# 06_-_FPGA_CONFIG_TEMP_MON.net
KiCad netlist of a schematic drawn in Altium Designer
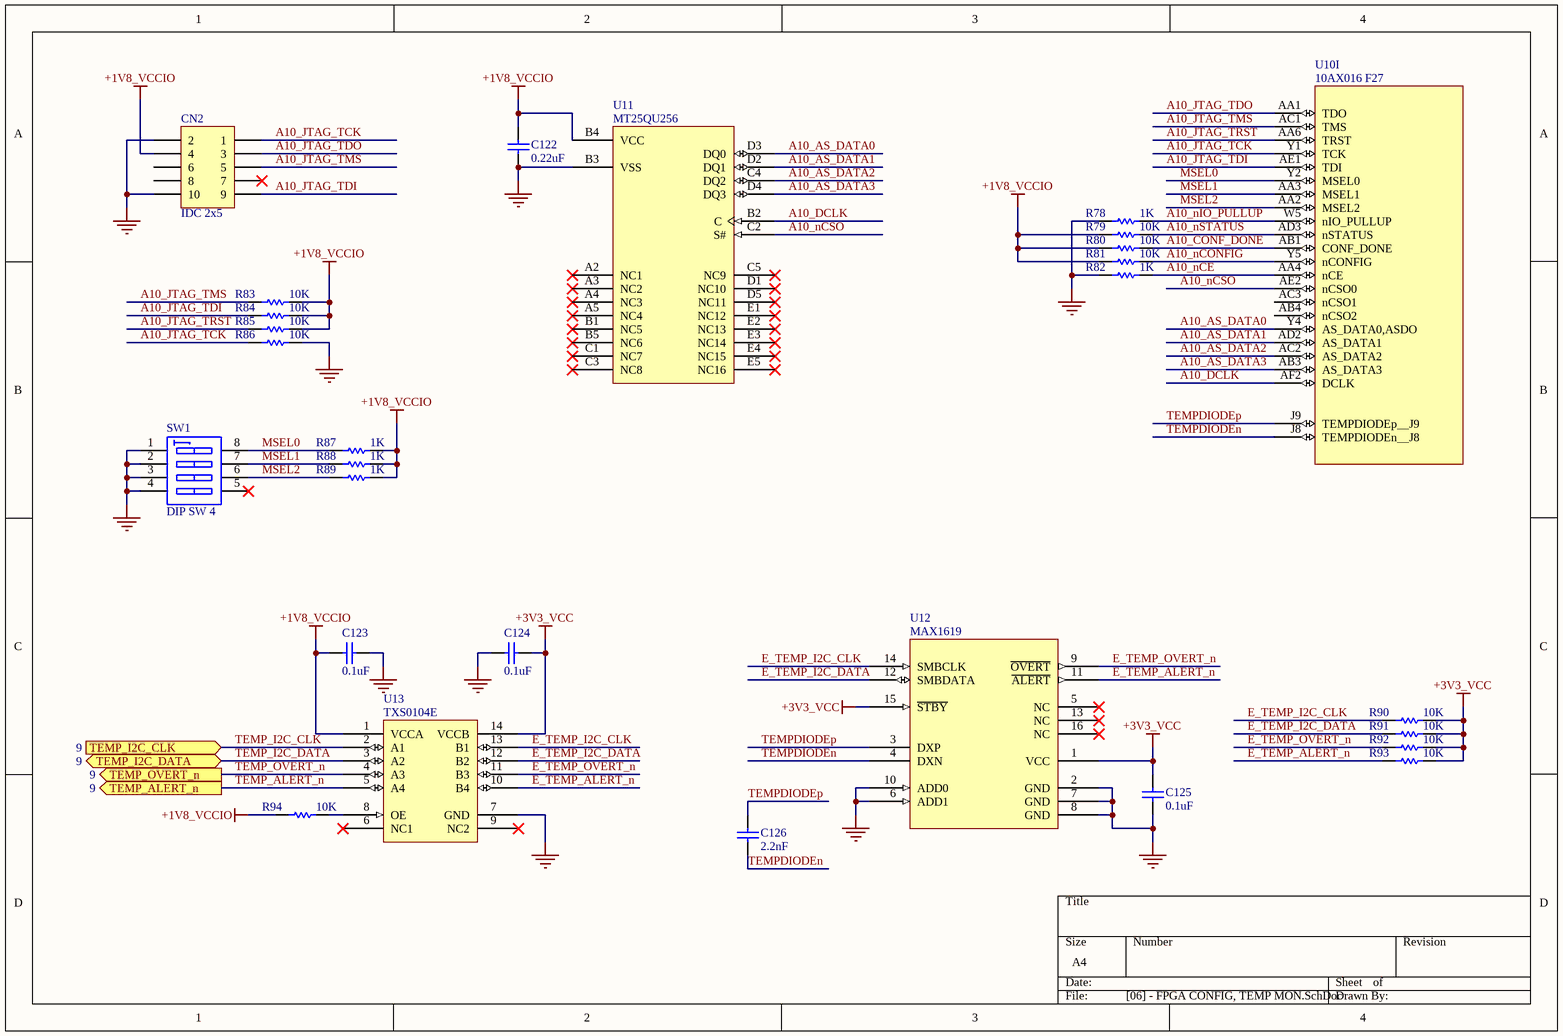
[diagram p0: [06] - FPGA CONFIG, TEMP MON.SchDoc]

(export (version "E")
  (design (tool "Eeschema 10.0.6"))
  (components
    (comp (ref "C122")
      (value "0.22uF")
      (footprint "0402_C")
      (description "Non-Pol SMD Capacitor")
      (libsource (lib "Passive Components") (part "Cap SMD"))
    )
    (comp (ref "C123")
      (value "0.1uF")
      (footprint "0805_C")
      (description "Non-Pol SMD Capacitor")
      (libsource (lib "Passive Components") (part "Cap SMD"))
    )
    (comp (ref "C124")
      (value "0.1uF")
      (footprint "0805_C")
      (description "Non-Pol SMD Capacitor")
      (libsource (lib "Passive Components") (part "Cap SMD"))
    )
    (comp (ref "C125")
      (value "0.1uF")
      (footprint "0805_C")
      (description "Non-Pol SMD Capacitor")
      (libsource (lib "Passive Components") (part "Cap SMD"))
    )
    (comp (ref "C126")
      (value "2.2nF")
      (footprint "0805_C")
      (description "Non-Pol SMD Capacitor")
      (libsource (lib "Passive Components") (part "Cap SMD"))
    )
    (comp (ref "CN2")
      (value "IDC 2x5")
      (footprint "IDC-BOX-2x5")
      (description "IDC Box, 5-Pin, Dual row")
      (libsource (lib "Connectors") (part "IDC 2x5"))
    )
    (comp (ref "R78")
      (value "1K")
      (footprint "0402_R")
      (description "SMD Resistor")
      (fields (field (name "TOLERANCE") "5%"))
      (libsource (lib "Passive Components") (part "Res SMD"))
    )
    (comp (ref "R79")
      (value "10K")
      (footprint "0402_R")
      (description "SMD Resistor")
      (fields (field (name "TOLERANCE") "5%"))
      (libsource (lib "Passive Components") (part "Res SMD"))
    )
    (comp (ref "R80")
      (value "10K")
      (footprint "0402_R")
      (description "SMD Resistor")
      (fields (field (name "TOLERANCE") "5%"))
      (libsource (lib "Passive Components") (part "Res SMD"))
    )
    (comp (ref "R81")
      (value "10K")
      (footprint "0402_R")
      (description "SMD Resistor")
      (fields (field (name "TOLERANCE") "5%"))
      (libsource (lib "Passive Components") (part "Res SMD"))
    )
    (comp (ref "R82")
      (value "1K")
      (footprint "0402_R")
      (description "SMD Resistor")
      (fields (field (name "TOLERANCE") "5%"))
      (libsource (lib "Passive Components") (part "Res SMD"))
    )
    (comp (ref "R83")
      (value "10K")
      (footprint "0402_R")
      (description "SMD Resistor")
      (fields (field (name "TOLERANCE") "5%"))
      (libsource (lib "Passive Components") (part "Res SMD"))
    )
    (comp (ref "R84")
      (value "10K")
      (footprint "0402_R")
      (description "SMD Resistor")
      (fields (field (name "TOLERANCE") "5%"))
      (libsource (lib "Passive Components") (part "Res SMD"))
    )
    (comp (ref "R85")
      (value "10K")
      (footprint "0402_R")
      (description "SMD Resistor")
      (fields (field (name "TOLERANCE") "5%"))
      (libsource (lib "Passive Components") (part "Res SMD"))
    )
    (comp (ref "R86")
      (value "10K")
      (footprint "0402_R")
      (description "SMD Resistor")
      (fields (field (name "TOLERANCE") "5%"))
      (libsource (lib "Passive Components") (part "Res SMD"))
    )
    (comp (ref "R87")
      (value "1K")
      (footprint "0402_R")
      (description "SMD Resistor")
      (fields (field (name "TOLERANCE") "5%"))
      (libsource (lib "Passive Components") (part "Res SMD"))
    )
    (comp (ref "R88")
      (value "1K")
      (footprint "0402_R")
      (description "SMD Resistor")
      (fields (field (name "TOLERANCE") "5%"))
      (libsource (lib "Passive Components") (part "Res SMD"))
    )
    (comp (ref "R89")
      (value "1K")
      (footprint "0402_R")
      (description "SMD Resistor")
      (fields (field (name "TOLERANCE") "5%"))
      (libsource (lib "Passive Components") (part "Res SMD"))
    )
    (comp (ref "R90")
      (value "10K")
      (footprint "0402_R")
      (description "SMD Resistor")
      (fields (field (name "TOLERANCE") "5%"))
      (libsource (lib "Passive Components") (part "Res SMD"))
    )
    (comp (ref "R91")
      (value "10K")
      (footprint "0402_R")
      (description "SMD Resistor")
      (fields (field (name "TOLERANCE") "5%"))
      (libsource (lib "Passive Components") (part "Res SMD"))
    )
    (comp (ref "R92")
      (value "10K")
      (footprint "0402_R")
      (description "SMD Resistor")
      (fields (field (name "TOLERANCE") "5%"))
      (libsource (lib "Passive Components") (part "Res SMD"))
    )
    (comp (ref "R93")
      (value "10K")
      (footprint "0402_R")
      (description "SMD Resistor")
      (fields (field (name "TOLERANCE") "5%"))
      (libsource (lib "Passive Components") (part "Res SMD"))
    )
    (comp (ref "R94")
      (value "10K")
      (footprint "0402_R")
      (description "SMD Resistor")
      (fields (field (name "TOLERANCE") "5%"))
      (libsource (lib "Passive Components") (part "Res SMD"))
    )
    (comp (ref "SW1")
      (value "DIP SW 4")
      (footprint "DIP-SW-4_1.27mm")
      (description "DIP Switch, 4 Position, SPST")
      (fields (field (name "MANUFACTURER PART NUM") "GDH04S04"))
      (libsource (lib "Passive Components") (part "DIP SW-4"))
    )
    (comp (ref "U10")
      (value "10AX016 F27")
      (footprint "FBGA672")
      (libsource (lib "Project_schlib") (part "10AX016"))
    )
    (comp (ref "U11")
      (value "MT25QU256")
      (description "Micron Serial NOR Flash Memory")
      (fields (field (name "MANUFACTURER PART NUM") "MT25QU256ABA8E12-1SIT"))
      (libsource (lib "Project_schlib") (part "MT25QU"))
    )
    (comp (ref "U12")
      (value "MAX1619")
      (description "Remote/Local Temperature Sensor")
      (libsource (lib "Project_schlib") (part "MAX1619"))
    )
    (comp (ref "U13")
      (value "TXS0104E")
      (description "4-Bit Bidirectional Voltage-Level Translator for Open-Drain and Push-Pull Applications")
      (libsource (lib "Project_schlib") (part "TXS0104E"))
    )
  )
  (nets
    (net (code "1") (name "+1V8_VCCIO") (class "Default")
      (node (ref "C122") (pin "2") (pinfunction "2_2") (pintype "passive"))
      (node (ref "C123") (pin "2") (pinfunction "2_2") (pintype "passive"))
      (node (ref "CN2") (pin "4") (pinfunction "4_4") (pintype "passive"))
      (node (ref "R79") (pin "1") (pinfunction "1_1") (pintype "passive"))
      (node (ref "R80") (pin "1") (pinfunction "1_1") (pintype "passive"))
      (node (ref "R81") (pin "1") (pinfunction "1_1") (pintype "passive"))
      (node (ref "R83") (pin "2") (pinfunction "2_2") (pintype "passive"))
      (node (ref "R84") (pin "2") (pinfunction "2_2") (pintype "passive"))
      (node (ref "R85") (pin "2") (pinfunction "2_2") (pintype "passive"))
      (node (ref "R87") (pin "2") (pinfunction "2_2") (pintype "passive"))
      (node (ref "R88") (pin "2") (pinfunction "2_2") (pintype "passive"))
      (node (ref "R89") (pin "2") (pinfunction "2_2") (pintype "passive"))
      (node (ref "R94") (pin "1") (pinfunction "1_1") (pintype "passive"))
      (node (ref "U11") (pin "B4") (pinfunction "VCC_B4") (pintype "power_in"))
      (node (ref "U13") (pin "1") (pinfunction "VCCA_1") (pintype "power_in"))
    )
    (net (code "2") (name "+3V3_VCC") (class "Default")
      (node (ref "C124") (pin "1") (pinfunction "1_1") (pintype "passive"))
      (node (ref "C125") (pin "2") (pinfunction "2_2") (pintype "passive"))
      (node (ref "R90") (pin "2") (pinfunction "2_2") (pintype "passive"))
      (node (ref "R91") (pin "2") (pinfunction "2_2") (pintype "passive"))
      (node (ref "R92") (pin "2") (pinfunction "2_2") (pintype "passive"))
      (node (ref "R93") (pin "2") (pinfunction "2_2") (pintype "passive"))
      (node (ref "U12") (pin "1") (pinfunction "VCC_1") (pintype "power_in"))
      (node (ref "U12") (pin "15") (pinfunction "~{STBY}_15") (pintype "input"))
      (node (ref "U13") (pin "14") (pinfunction "VCCB_14") (pintype "power_in"))
    )
    (net (code "3") (name "/A10_AS_DATA0") (class "Default")
      (node (ref "U10") (pin "Y4") (pinfunction "AS_DATA0,ASDO_Y4") (pintype "bidirectional"))
      (node (ref "U11") (pin "D3") (pinfunction "DQ0_D3") (pintype "bidirectional"))
    )
    (net (code "4") (name "/A10_AS_DATA1") (class "Default")
      (node (ref "U10") (pin "AD2") (pinfunction "AS_DATA1_AD2") (pintype "bidirectional"))
      (node (ref "U11") (pin "D2") (pinfunction "DQ1_D2") (pintype "bidirectional"))
    )
    (net (code "5") (name "/A10_AS_DATA2") (class "Default")
      (node (ref "U10") (pin "AC2") (pinfunction "AS_DATA2_AC2") (pintype "bidirectional"))
      (node (ref "U11") (pin "C4") (pinfunction "DQ2_C4") (pintype "bidirectional"))
    )
    (net (code "6") (name "/A10_AS_DATA3") (class "Default")
      (node (ref "U10") (pin "AB3") (pinfunction "AS_DATA3_AB3") (pintype "bidirectional"))
      (node (ref "U11") (pin "D4") (pinfunction "DQ3_D4") (pintype "bidirectional"))
    )
    (net (code "7") (name "/A10_CONF_DONE") (class "Default")
      (node (ref "R80") (pin "2") (pinfunction "2_2") (pintype "passive"))
      (node (ref "U10") (pin "AB1") (pinfunction "CONF_DONE_AB1") (pintype "bidirectional"))
    )
    (net (code "8") (name "/A10_DCLK") (class "Default")
      (node (ref "U10") (pin "AF2") (pinfunction "DCLK_AF2") (pintype "bidirectional"))
      (node (ref "U11") (pin "B2") (pinfunction "C_B2") (pintype "input"))
    )
    (net (code "9") (name "/A10_JTAG_TCK") (class "Default")
      (node (ref "CN2") (pin "1") (pinfunction "1_1") (pintype "passive"))
      (node (ref "R86") (pin "1") (pinfunction "1_1") (pintype "passive"))
      (node (ref "U10") (pin "Y1") (pinfunction "TCK_Y1") (pintype "bidirectional"))
    )
    (net (code "10") (name "/A10_JTAG_TDI") (class "Default")
      (node (ref "CN2") (pin "9") (pinfunction "9_9") (pintype "passive"))
      (node (ref "R84") (pin "1") (pinfunction "1_1") (pintype "passive"))
      (node (ref "U10") (pin "AE1") (pinfunction "TDI_AE1") (pintype "bidirectional"))
    )
    (net (code "11") (name "/A10_JTAG_TDO") (class "Default")
      (node (ref "CN2") (pin "3") (pinfunction "3_3") (pintype "passive"))
      (node (ref "U10") (pin "AA1") (pinfunction "TDO_AA1") (pintype "bidirectional"))
    )
    (net (code "12") (name "/A10_JTAG_TMS") (class "Default")
      (node (ref "CN2") (pin "5") (pinfunction "5_5") (pintype "passive"))
      (node (ref "R83") (pin "1") (pinfunction "1_1") (pintype "passive"))
      (node (ref "U10") (pin "AC1") (pinfunction "TMS_AC1") (pintype "bidirectional"))
    )
    (net (code "13") (name "/A10_JTAG_TRST") (class "Default")
      (node (ref "R85") (pin "1") (pinfunction "1_1") (pintype "passive"))
      (node (ref "U10") (pin "AA6") (pinfunction "TRST_AA6") (pintype "bidirectional"))
    )
    (net (code "14") (name "/A10_nCE") (class "Default")
      (node (ref "R82") (pin "2") (pinfunction "2_2") (pintype "passive"))
      (node (ref "U10") (pin "AA4") (pinfunction "nCE_AA4") (pintype "bidirectional"))
    )
    (net (code "15") (name "/A10_nCONFIG") (class "Default")
      (node (ref "R81") (pin "2") (pinfunction "2_2") (pintype "passive"))
      (node (ref "U10") (pin "Y5") (pinfunction "nCONFIG_Y5") (pintype "bidirectional"))
    )
    (net (code "16") (name "/A10_nCSO") (class "Default")
      (node (ref "U10") (pin "AE2") (pinfunction "nCSO0_AE2") (pintype "bidirectional"))
      (node (ref "U11") (pin "C2") (pinfunction "S#_C2") (pintype "input"))
    )
    (net (code "17") (name "/A10_nIO_PULLUP") (class "Default")
      (node (ref "R78") (pin "2") (pinfunction "2_2") (pintype "passive"))
      (node (ref "U10") (pin "W5") (pinfunction "nIO_PULLUP_W5") (pintype "bidirectional"))
    )
    (net (code "18") (name "/A10_nSTATUS") (class "Default")
      (node (ref "R79") (pin "2") (pinfunction "2_2") (pintype "passive"))
      (node (ref "U10") (pin "AD3") (pinfunction "nSTATUS_AD3") (pintype "bidirectional"))
    )
    (net (code "19") (name "/E_TEMP_ALERT_n") (class "Default")
      (node (ref "R93") (pin "1") (pinfunction "1_1") (pintype "passive"))
      (node (ref "U12") (pin "11") (pinfunction "~{ALERT}_11") (pintype "output"))
      (node (ref "U13") (pin "10") (pinfunction "B4_10") (pintype "bidirectional"))
    )
    (net (code "20") (name "/E_TEMP_I2C_CLK") (class "Default")
      (node (ref "R90") (pin "1") (pinfunction "1_1") (pintype "passive"))
      (node (ref "U12") (pin "14") (pinfunction "SMBCLK_14") (pintype "input"))
      (node (ref "U13") (pin "13") (pinfunction "B1_13") (pintype "bidirectional"))
    )
    (net (code "21") (name "/E_TEMP_I2C_DATA") (class "Default")
      (node (ref "R91") (pin "1") (pinfunction "1_1") (pintype "passive"))
      (node (ref "U12") (pin "12") (pinfunction "SMBDATA_12") (pintype "bidirectional"))
      (node (ref "U13") (pin "12") (pinfunction "B2_12") (pintype "bidirectional"))
    )
    (net (code "22") (name "/E_TEMP_OVERT_n") (class "Default")
      (node (ref "R92") (pin "1") (pinfunction "1_1") (pintype "passive"))
      (node (ref "U12") (pin "9") (pinfunction "~{OVERT}_9") (pintype "output"))
      (node (ref "U13") (pin "11") (pinfunction "B3_11") (pintype "bidirectional"))
    )
    (net (code "23") (name "/MSEL0") (class "Default")
      (node (ref "R87") (pin "1") (pinfunction "1_1") (pintype "passive"))
      (node (ref "SW1") (pin "8") (pinfunction "B3_8") (pintype "passive"))
      (node (ref "U10") (pin "Y2") (pinfunction "MSEL0_Y2") (pintype "bidirectional"))
    )
    (net (code "24") (name "/MSEL1") (class "Default")
      (node (ref "R88") (pin "1") (pinfunction "1_1") (pintype "passive"))
      (node (ref "SW1") (pin "7") (pinfunction "B4_7") (pintype "passive"))
      (node (ref "U10") (pin "AA3") (pinfunction "MSEL1_AA3") (pintype "bidirectional"))
    )
    (net (code "25") (name "/MSEL2") (class "Default")
      (node (ref "R89") (pin "1") (pinfunction "1_1") (pintype "passive"))
      (node (ref "SW1") (pin "6") (pinfunction "B5_6") (pintype "passive"))
      (node (ref "U10") (pin "AA2") (pinfunction "MSEL2_AA2") (pintype "bidirectional"))
    )
    (net (code "26") (name "/TEMPDIODEn") (class "Default")
      (node (ref "C126") (pin "1") (pinfunction "1_1") (pintype "passive"))
      (node (ref "U10") (pin "J8") (pinfunction "TEMPDIODEn__J8_J8") (pintype "bidirectional"))
      (node (ref "U12") (pin "4") (pinfunction "DXN_4") (pintype "passive"))
    )
    (net (code "27") (name "/TEMPDIODEp") (class "Default")
      (node (ref "C126") (pin "2") (pinfunction "2_2") (pintype "passive"))
      (node (ref "U10") (pin "J9") (pinfunction "TEMPDIODEp__J9_J9") (pintype "bidirectional"))
      (node (ref "U12") (pin "3") (pinfunction "DXP_3") (pintype "passive"))
    )
    (net (code "28") (name "/TEMP_ALERT_n") (class "Default")
      (node (ref "U13") (pin "5") (pinfunction "A4_5") (pintype "bidirectional"))
    )
    (net (code "29") (name "/TEMP_I2C_CLK") (class "Default")
      (node (ref "U13") (pin "2") (pinfunction "A1_2") (pintype "bidirectional"))
    )
    (net (code "30") (name "/TEMP_I2C_DATA") (class "Default")
      (node (ref "U13") (pin "3") (pinfunction "A2_3") (pintype "bidirectional"))
    )
    (net (code "31") (name "/TEMP_OVERT_n") (class "Default")
      (node (ref "U13") (pin "4") (pinfunction "A3_4") (pintype "bidirectional"))
    )
    (net (code "32") (name "GND") (class "Default")
      (node (ref "C122") (pin "1") (pinfunction "1_1") (pintype "passive"))
      (node (ref "C123") (pin "1") (pinfunction "1_1") (pintype "passive"))
      (node (ref "C124") (pin "2") (pinfunction "2_2") (pintype "passive"))
      (node (ref "C125") (pin "1") (pinfunction "1_1") (pintype "passive"))
      (node (ref "CN2") (pin "10") (pinfunction "10_10") (pintype "passive"))
      (node (ref "CN2") (pin "2") (pinfunction "2_2") (pintype "passive"))
      (node (ref "R78") (pin "1") (pinfunction "1_1") (pintype "passive"))
      (node (ref "R82") (pin "1") (pinfunction "1_1") (pintype "passive"))
      (node (ref "R86") (pin "2") (pinfunction "2_2") (pintype "passive"))
      (node (ref "SW1") (pin "1") (pinfunction "A1_1") (pintype "passive"))
      (node (ref "SW1") (pin "2") (pinfunction "A2_2") (pintype "passive"))
      (node (ref "SW1") (pin "3") (pinfunction "A3_3") (pintype "passive"))
      (node (ref "SW1") (pin "4") (pinfunction "A4_4") (pintype "passive"))
      (node (ref "U11") (pin "B3") (pinfunction "VSS_B3") (pintype "power_in"))
      (node (ref "U12") (pin "10") (pinfunction "ADD0_10") (pintype "input"))
      (node (ref "U12") (pin "2") (pinfunction "GND_2") (pintype "power_in"))
      (node (ref "U12") (pin "6") (pinfunction "ADD1_6") (pintype "input"))
      (node (ref "U12") (pin "7") (pinfunction "GND_7") (pintype "power_in"))
      (node (ref "U12") (pin "8") (pinfunction "GND_8") (pintype "power_in"))
      (node (ref "U13") (pin "7") (pinfunction "GND_7") (pintype "power_in"))
    )
    (net (code "33") (name "Net-(U13-OE)") (class "Default")
      (node (ref "R94") (pin "2") (pinfunction "2_2") (pintype "passive"))
      (node (ref "U13") (pin "8") (pinfunction "OE_8") (pintype "input"))
    )
    (net (code "34") (name "unconnected-(CN2-Pad6)") (class "Default")
      (node (ref "CN2") (pin "6") (pinfunction "6_6") (pintype "passive"))
    )
    (net (code "35") (name "unconnected-(CN2-Pad7)") (class "Default")
      (node (ref "CN2") (pin "7") (pinfunction "7_7") (pintype "passive+no_connect"))
    )
    (net (code "36") (name "unconnected-(CN2-Pad8)") (class "Default")
      (node (ref "CN2") (pin "8") (pinfunction "8_8") (pintype "passive"))
    )
    (net (code "37") (name "unconnected-(SW1-A5-Pad5)") (class "Default")
      (node (ref "SW1") (pin "5") (pinfunction "A5_5") (pintype "passive+no_connect"))
    )
    (net (code "38") (name "unconnected-(U10I-nCSO1-PadAC3)") (class "Default")
      (node (ref "U10") (pin "AC3") (pinfunction "nCSO1_AC3") (pintype "bidirectional"))
    )
    (net (code "39") (name "unconnected-(U10I-nCSO2-PadAB4)") (class "Default")
      (node (ref "U10") (pin "AB4") (pinfunction "nCSO2_AB4") (pintype "bidirectional"))
    )
    (net (code "40") (name "unconnected-(U11-NC1-PadA2)") (class "Default")
      (node (ref "U11") (pin "A2") (pinfunction "NC1_A2") (pintype "passive+no_connect"))
    )
    (net (code "41") (name "unconnected-(U11-NC2-PadA3)") (class "Default")
      (node (ref "U11") (pin "A3") (pinfunction "NC2_A3") (pintype "passive+no_connect"))
    )
    (net (code "42") (name "unconnected-(U11-NC3-PadA4)") (class "Default")
      (node (ref "U11") (pin "A4") (pinfunction "NC3_A4") (pintype "passive+no_connect"))
    )
    (net (code "43") (name "unconnected-(U11-NC4-PadA5)") (class "Default")
      (node (ref "U11") (pin "A5") (pinfunction "NC4_A5") (pintype "passive+no_connect"))
    )
    (net (code "44") (name "unconnected-(U11-NC5-PadB1)") (class "Default")
      (node (ref "U11") (pin "B1") (pinfunction "NC5_B1") (pintype "passive+no_connect"))
    )
    (net (code "45") (name "unconnected-(U11-NC6-PadB5)") (class "Default")
      (node (ref "U11") (pin "B5") (pinfunction "NC6_B5") (pintype "passive+no_connect"))
    )
    (net (code "46") (name "unconnected-(U11-NC7-PadC1)") (class "Default")
      (node (ref "U11") (pin "C1") (pinfunction "NC7_C1") (pintype "passive+no_connect"))
    )
    (net (code "47") (name "unconnected-(U11-NC8-PadC3)") (class "Default")
      (node (ref "U11") (pin "C3") (pinfunction "NC8_C3") (pintype "passive+no_connect"))
    )
    (net (code "48") (name "unconnected-(U11-NC9-PadC5)") (class "Default")
      (node (ref "U11") (pin "C5") (pinfunction "NC9_C5") (pintype "passive+no_connect"))
    )
    (net (code "49") (name "unconnected-(U11-NC10-PadD1)") (class "Default")
      (node (ref "U11") (pin "D1") (pinfunction "NC10_D1") (pintype "passive+no_connect"))
    )
    (net (code "50") (name "unconnected-(U11-NC11-PadD5)") (class "Default")
      (node (ref "U11") (pin "D5") (pinfunction "NC11_D5") (pintype "passive+no_connect"))
    )
    (net (code "51") (name "unconnected-(U11-NC12-PadE1)") (class "Default")
      (node (ref "U11") (pin "E1") (pinfunction "NC12_E1") (pintype "passive+no_connect"))
    )
    (net (code "52") (name "unconnected-(U11-NC13-PadE2)") (class "Default")
      (node (ref "U11") (pin "E2") (pinfunction "NC13_E2") (pintype "passive+no_connect"))
    )
    (net (code "53") (name "unconnected-(U11-NC14-PadE3)") (class "Default")
      (node (ref "U11") (pin "E3") (pinfunction "NC14_E3") (pintype "passive+no_connect"))
    )
    (net (code "54") (name "unconnected-(U11-NC15-PadE4)") (class "Default")
      (node (ref "U11") (pin "E4") (pinfunction "NC15_E4") (pintype "passive+no_connect"))
    )
    (net (code "55") (name "unconnected-(U11-NC16-PadE5)") (class "Default")
      (node (ref "U11") (pin "E5") (pinfunction "NC16_E5") (pintype "passive+no_connect"))
    )
    (net (code "56") (name "unconnected-(U12-NC-Pad5)") (class "Default")
      (node (ref "U12") (pin "5") (pinfunction "NC_5") (pintype "passive+no_connect"))
    )
    (net (code "57") (name "unconnected-(U12-NC-Pad13)") (class "Default")
      (node (ref "U12") (pin "13") (pinfunction "NC_13") (pintype "passive+no_connect"))
    )
    (net (code "58") (name "unconnected-(U12-NC-Pad16)") (class "Default")
      (node (ref "U12") (pin "16") (pinfunction "NC_16") (pintype "passive+no_connect"))
    )
    (net (code "59") (name "unconnected-(U13-NC1-Pad6)") (class "Default")
      (node (ref "U13") (pin "6") (pinfunction "NC1_6") (pintype "passive+no_connect"))
    )
    (net (code "60") (name "unconnected-(U13-NC2-Pad9)") (class "Default")
      (node (ref "U13") (pin "9") (pinfunction "NC2_9") (pintype "passive+no_connect"))
    )
  )
)
